# XC888.net
KiCad netlist of a schematic drawn in Altium Designer
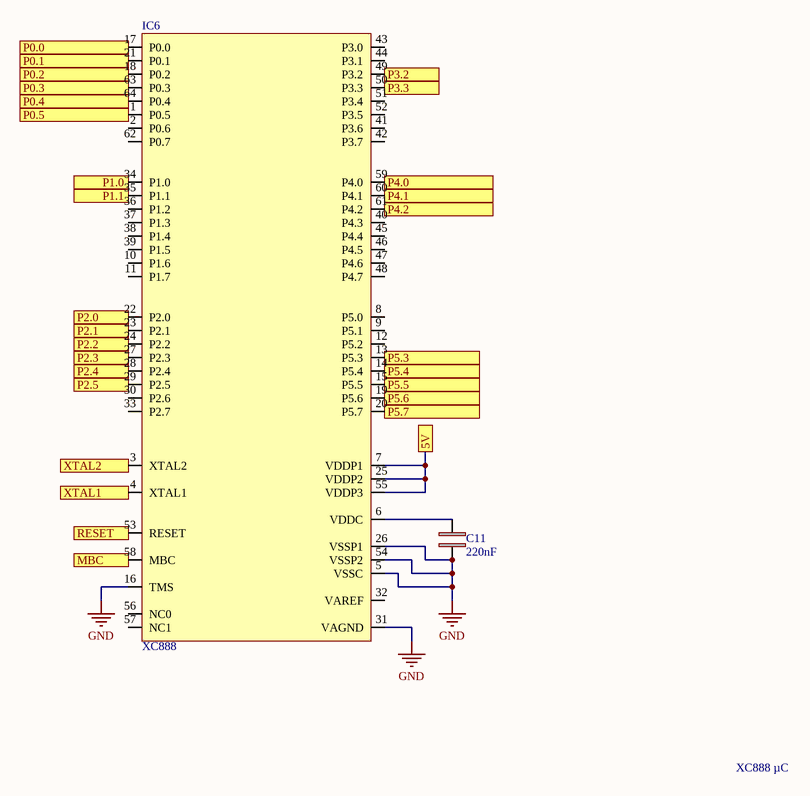
[diagram p0: XC888.SchDoc]

(export (version "E")
  (design (tool "Eeschema 10.0.6"))
  (components
    (comp (ref "C11")
      (value "220nF")
      (footprint "C0805C224K5RACTU")
      (description "0805 C 220nF Ceramic Multilayer Capacitor; 50 VDC; +125degC; X7R Dielec; +/-10%")
      (fields
        (field (name "MANUFACTURER") "KEMET")
        (field (name "MANUFACTURER PART NUMBER") "C0805C224K5RACTU")
      )
      (libsource (lib "Tama_Schlib") (part "C0805C224K5RACTU"))
    )
    (comp (ref "IC6")
      (value "XC888")
      (footprint "XC888 - 3")
      (description "MCU 8-Bit XC800 8051 CISC 32KB Flash 2.5V/5V 64-Pin LQFP T/R")
      (fields
        (field (name "MANUFACTURER") "Infineon")
        (field (name "MANUFACTURER PART NUMBER") "XC8888FFI5VACFXUMA1")
      )
      (libsource (lib "Tama_Schlib") (part "XC8888FFI5VACFXUMA1"))
    )
  )
  (nets
    (net (code "1") (name "/5V") (class "Default")
      (node (ref "IC6") (pin "25") (pinfunction "VDDP2_25") (pintype "passive"))
      (node (ref "IC6") (pin "55") (pinfunction "VDDP3_55") (pintype "passive"))
      (node (ref "IC6") (pin "7") (pinfunction "VDDP1_7") (pintype "passive"))
    )
    (net (code "2") (name "/MBC") (class "Default")
      (node (ref "IC6") (pin "58") (pinfunction "MBC_58") (pintype "passive"))
    )
    (net (code "3") (name "/P0.0") (class "Default")
      (node (ref "IC6") (pin "17") (pinfunction "P0.0_17") (pintype "passive"))
    )
    (net (code "4") (name "/P0.1") (class "Default")
      (node (ref "IC6") (pin "21") (pinfunction "P0.1_21") (pintype "passive"))
    )
    (net (code "5") (name "/P0.2") (class "Default")
      (node (ref "IC6") (pin "18") (pinfunction "P0.2_18") (pintype "passive"))
    )
    (net (code "6") (name "/P0.3") (class "Default")
      (node (ref "IC6") (pin "63") (pinfunction "P0.3_63") (pintype "passive"))
    )
    (net (code "7") (name "/P0.4") (class "Default")
      (node (ref "IC6") (pin "64") (pinfunction "P0.4_64") (pintype "passive"))
    )
    (net (code "8") (name "/P0.5") (class "Default")
      (node (ref "IC6") (pin "1") (pinfunction "P0.5_1") (pintype "passive"))
    )
    (net (code "9") (name "/P1.0") (class "Default")
      (node (ref "IC6") (pin "34") (pinfunction "P1.0_34") (pintype "passive"))
    )
    (net (code "10") (name "/P1.1") (class "Default")
      (node (ref "IC6") (pin "35") (pinfunction "P1.1_35") (pintype "passive"))
    )
    (net (code "11") (name "/P2.0") (class "Default")
      (node (ref "IC6") (pin "22") (pinfunction "P2.0_22") (pintype "passive"))
    )
    (net (code "12") (name "/P2.1") (class "Default")
      (node (ref "IC6") (pin "23") (pinfunction "P2.1_23") (pintype "passive"))
    )
    (net (code "13") (name "/P2.2") (class "Default")
      (node (ref "IC6") (pin "24") (pinfunction "P2.2_24") (pintype "passive"))
    )
    (net (code "14") (name "/P2.3") (class "Default")
      (node (ref "IC6") (pin "27") (pinfunction "P2.3_27") (pintype "passive"))
    )
    (net (code "15") (name "/P2.4") (class "Default")
      (node (ref "IC6") (pin "28") (pinfunction "P2.4_28") (pintype "passive"))
    )
    (net (code "16") (name "/P2.5") (class "Default")
      (node (ref "IC6") (pin "29") (pinfunction "P2.5_29") (pintype "passive"))
    )
    (net (code "17") (name "/P3.2") (class "Default")
      (node (ref "IC6") (pin "49") (pinfunction "P3.2_49") (pintype "passive"))
    )
    (net (code "18") (name "/P3.3") (class "Default")
      (node (ref "IC6") (pin "50") (pinfunction "P3.3_50") (pintype "passive"))
    )
    (net (code "19") (name "/P4.0") (class "Default")
      (node (ref "IC6") (pin "59") (pinfunction "P4.0_59") (pintype "passive"))
    )
    (net (code "20") (name "/P4.1") (class "Default")
      (node (ref "IC6") (pin "60") (pinfunction "P4.1_60") (pintype "passive"))
    )
    (net (code "21") (name "/P4.2") (class "Default")
      (node (ref "IC6") (pin "61") (pinfunction "P4.2_61") (pintype "passive"))
    )
    (net (code "22") (name "/P5.3") (class "Default")
      (node (ref "IC6") (pin "13") (pinfunction "P5.3_13") (pintype "passive"))
    )
    (net (code "23") (name "/P5.4") (class "Default")
      (node (ref "IC6") (pin "14") (pinfunction "P5.4_14") (pintype "passive"))
    )
    (net (code "24") (name "/P5.5") (class "Default")
      (node (ref "IC6") (pin "15") (pinfunction "P5.5_15") (pintype "passive"))
    )
    (net (code "25") (name "/P5.6") (class "Default")
      (node (ref "IC6") (pin "19") (pinfunction "P5.6_19") (pintype "passive"))
    )
    (net (code "26") (name "/P5.7") (class "Default")
      (node (ref "IC6") (pin "20") (pinfunction "P5.7_20") (pintype "passive"))
    )
    (net (code "27") (name "/RESET") (class "Default")
      (node (ref "IC6") (pin "53") (pinfunction "RESET_53") (pintype "passive"))
    )
    (net (code "28") (name "/XTAL1") (class "Default")
      (node (ref "IC6") (pin "4") (pinfunction "XTAL1_4") (pintype "passive"))
    )
    (net (code "29") (name "/XTAL2") (class "Default")
      (node (ref "IC6") (pin "3") (pinfunction "XTAL2_3") (pintype "passive"))
    )
    (net (code "30") (name "GND") (class "Default")
      (node (ref "C11") (pin "2") (pinfunction "2_2") (pintype "passive"))
      (node (ref "IC6") (pin "16") (pinfunction "TMS_16") (pintype "passive"))
      (node (ref "IC6") (pin "26") (pinfunction "VSSP1_26") (pintype "passive"))
      (node (ref "IC6") (pin "31") (pinfunction "VAGND_31") (pintype "passive"))
      (node (ref "IC6") (pin "5") (pinfunction "VSSC_5") (pintype "passive"))
      (node (ref "IC6") (pin "54") (pinfunction "VSSP2_54") (pintype "passive"))
    )
    (net (code "31") (name "Net-(IC6-VDDC)") (class "Default")
      (node (ref "C11") (pin "1") (pinfunction "1_1") (pintype "passive"))
      (node (ref "IC6") (pin "6") (pinfunction "VDDC_6") (pintype "passive"))
    )
    (net (code "32") (name "unconnected-(IC6-NC0-Pad56)") (class "Default")
      (node (ref "IC6") (pin "56") (pinfunction "NC0_56") (pintype "passive"))
    )
    (net (code "33") (name "unconnected-(IC6-NC1-Pad57)") (class "Default")
      (node (ref "IC6") (pin "57") (pinfunction "NC1_57") (pintype "passive"))
    )
    (net (code "34") (name "unconnected-(IC6-P0.6-Pad2)") (class "Default")
      (node (ref "IC6") (pin "2") (pinfunction "P0.6_2") (pintype "passive"))
    )
    (net (code "35") (name "unconnected-(IC6-P0.7-Pad62)") (class "Default")
      (node (ref "IC6") (pin "62") (pinfunction "P0.7_62") (pintype "passive"))
    )
    (net (code "36") (name "unconnected-(IC6-P1.2-Pad36)") (class "Default")
      (node (ref "IC6") (pin "36") (pinfunction "P1.2_36") (pintype "passive"))
    )
    (net (code "37") (name "unconnected-(IC6-P1.3-Pad37)") (class "Default")
      (node (ref "IC6") (pin "37") (pinfunction "P1.3_37") (pintype "passive"))
    )
    (net (code "38") (name "unconnected-(IC6-P1.4-Pad38)") (class "Default")
      (node (ref "IC6") (pin "38") (pinfunction "P1.4_38") (pintype "passive"))
    )
    (net (code "39") (name "unconnected-(IC6-P1.5-Pad39)") (class "Default")
      (node (ref "IC6") (pin "39") (pinfunction "P1.5_39") (pintype "passive"))
    )
    (net (code "40") (name "unconnected-(IC6-P1.6-Pad10)") (class "Default")
      (node (ref "IC6") (pin "10") (pinfunction "P1.6_10") (pintype "passive"))
    )
    (net (code "41") (name "unconnected-(IC6-P1.7-Pad11)") (class "Default")
      (node (ref "IC6") (pin "11") (pinfunction "P1.7_11") (pintype "passive"))
    )
    (net (code "42") (name "unconnected-(IC6-P2.6-Pad30)") (class "Default")
      (node (ref "IC6") (pin "30") (pinfunction "P2.6_30") (pintype "passive"))
    )
    (net (code "43") (name "unconnected-(IC6-P2.7-Pad33)") (class "Default")
      (node (ref "IC6") (pin "33") (pinfunction "P2.7_33") (pintype "passive"))
    )
    (net (code "44") (name "unconnected-(IC6-P3.0-Pad43)") (class "Default")
      (node (ref "IC6") (pin "43") (pinfunction "P3.0_43") (pintype "passive"))
    )
    (net (code "45") (name "unconnected-(IC6-P3.1-Pad44)") (class "Default")
      (node (ref "IC6") (pin "44") (pinfunction "P3.1_44") (pintype "passive"))
    )
    (net (code "46") (name "unconnected-(IC6-P3.4-Pad51)") (class "Default")
      (node (ref "IC6") (pin "51") (pinfunction "P3.4_51") (pintype "passive"))
    )
    (net (code "47") (name "unconnected-(IC6-P3.5-Pad52)") (class "Default")
      (node (ref "IC6") (pin "52") (pinfunction "P3.5_52") (pintype "passive"))
    )
    (net (code "48") (name "unconnected-(IC6-P3.6-Pad41)") (class "Default")
      (node (ref "IC6") (pin "41") (pinfunction "P3.6_41") (pintype "passive"))
    )
    (net (code "49") (name "unconnected-(IC6-P3.7-Pad42)") (class "Default")
      (node (ref "IC6") (pin "42") (pinfunction "P3.7_42") (pintype "passive"))
    )
    (net (code "50") (name "unconnected-(IC6-P4.3-Pad40)") (class "Default")
      (node (ref "IC6") (pin "40") (pinfunction "P4.3_40") (pintype "passive"))
    )
    (net (code "51") (name "unconnected-(IC6-P4.4-Pad45)") (class "Default")
      (node (ref "IC6") (pin "45") (pinfunction "P4.4_45") (pintype "passive"))
    )
    (net (code "52") (name "unconnected-(IC6-P4.5-Pad46)") (class "Default")
      (node (ref "IC6") (pin "46") (pinfunction "P4.5_46") (pintype "passive"))
    )
    (net (code "53") (name "unconnected-(IC6-P4.6-Pad47)") (class "Default")
      (node (ref "IC6") (pin "47") (pinfunction "P4.6_47") (pintype "passive"))
    )
    (net (code "54") (name "unconnected-(IC6-P4.7-Pad48)") (class "Default")
      (node (ref "IC6") (pin "48") (pinfunction "P4.7_48") (pintype "passive"))
    )
    (net (code "55") (name "unconnected-(IC6-P5.0-Pad8)") (class "Default")
      (node (ref "IC6") (pin "8") (pinfunction "P5.0_8") (pintype "passive"))
    )
    (net (code "56") (name "unconnected-(IC6-P5.1-Pad9)") (class "Default")
      (node (ref "IC6") (pin "9") (pinfunction "P5.1_9") (pintype "passive"))
    )
    (net (code "57") (name "unconnected-(IC6-P5.2-Pad12)") (class "Default")
      (node (ref "IC6") (pin "12") (pinfunction "P5.2_12") (pintype "passive"))
    )
    (net (code "58") (name "unconnected-(IC6-VAREF-Pad32)") (class "Default")
      (node (ref "IC6") (pin "32") (pinfunction "VAREF_32") (pintype "passive"))
    )
  )
)
